# sub_module.net
KiCad netlist of a schematic drawn in EAGLE
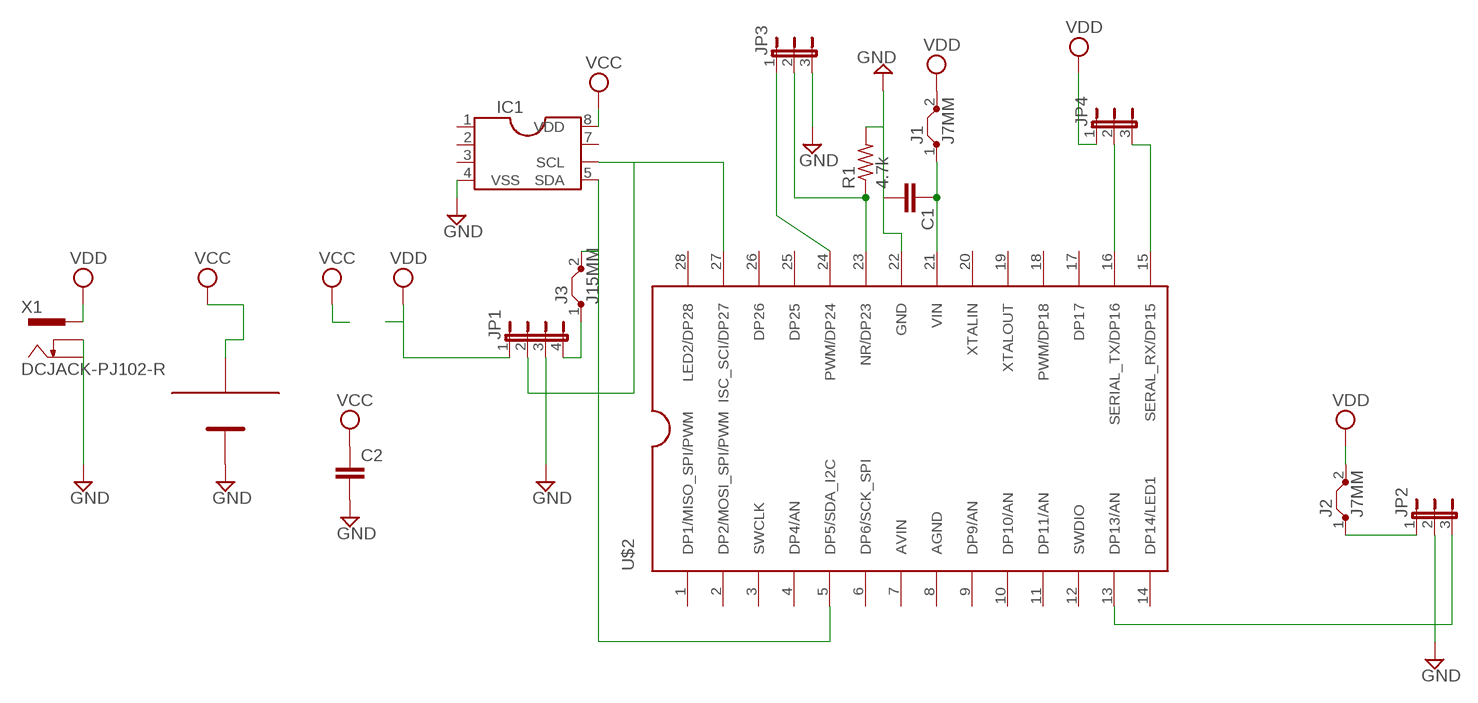
[diagram p0: schematic, sheet 1]

(export (version "E")
  (design (tool "Eeschema 10.0.6"))
  (components
    (comp (ref "C1")
      (value "C-EUC2012")
      (footprint "eagle-import:C2012")
      (libsource (lib "eagle-import") (part "C-EUC2012"))
    )
    (comp (ref "C2")
      (value "C-EUC2012")
      (footprint "eagle-import:C2012")
      (libsource (lib "eagle-import") (part "C-EUC2012"))
    )
    (comp (ref "IC1")
      (value "DIL8S")
      (footprint "eagle-import:SOCKET-08")
      (libsource (lib "eagle-import") (part "DIL8S"))
    )
    (comp (ref "J1")
      (value "J7MM")
      (footprint "eagle-import:07")
      (libsource (lib "eagle-import") (part "J7MM"))
    )
    (comp (ref "J2")
      (value "J7MM")
      (footprint "eagle-import:07")
      (libsource (lib "eagle-import") (part "J7MM"))
    )
    (comp (ref "J3")
      (value "J15MM")
      (footprint "eagle-import:15")
      (libsource (lib "eagle-import") (part "J15MM"))
    )
    (comp (ref "JP1")
      (value "JP4E")
      (footprint "eagle-import:JP4")
      (libsource (lib "eagle-import") (part "JP4E"))
    )
    (comp (ref "JP2")
      (value "JP2E")
      (footprint "eagle-import:JP2")
      (libsource (lib "eagle-import") (part "JP2E"))
    )
    (comp (ref "JP3")
      (value "JP2E")
      (footprint "eagle-import:JP2")
      (libsource (lib "eagle-import") (part "JP2E"))
    )
    (comp (ref "JP4")
      (value "JP2E")
      (footprint "eagle-import:JP2")
      (libsource (lib "eagle-import") (part "JP2E"))
    )
    (comp (ref "R1")
      (value "4.7k")
      (footprint "eagle-import:0207_2V")
      (libsource (lib "eagle-import") (part "R-US_0207/2V"))
    )
    (comp (ref "U$1")
      (value "CR2032-HOLDER2")
      (footprint "eagle-import:CR2032-HOLDER2")
      (libsource (lib "eagle-import") (part "CR2032-HOLDER2"))
    )
    (comp (ref "U$2")
      (value "LPC1114FDH28")
      (footprint "eagle-import:TSSOP28")
      (libsource (lib "eagle-import") (part "LPC1114FDH28"))
    )
    (comp (ref "X1")
      (value "DCJACK-PJ102-R")
      (footprint "eagle-import:PJ-102-R")
      (libsource (lib "eagle-import") (part "DCJACK-PJ102-R"))
    )
  )
  (nets
    (net (code "1") (name "/AGND") (class "Default")
      (node (ref "U$2") (pin "8") (pinfunction "AGND_8") (pintype "power_in"))
    )
    (net (code "2") (name "/AVIN") (class "Default")
      (node (ref "U$2") (pin "7") (pinfunction "AVIN_7") (pintype "power_in"))
    )
    (net (code "3") (name "GND") (class "Default")
      (node (ref "C1") (pin "2") (pinfunction "2_2") (pintype "passive"))
      (node (ref "C2") (pin "2") (pinfunction "2_2") (pintype "passive"))
      (node (ref "IC1") (pin "4") (pinfunction "VSS_4") (pintype "passive"))
      (node (ref "JP1") (pin "3") (pinfunction "3_3") (pintype "passive"))
      (node (ref "JP2") (pin "2") (pinfunction "2_2") (pintype "passive"))
      (node (ref "JP3") (pin "3") (pinfunction "3_3") (pintype "passive"))
      (node (ref "R1") (pin "2") (pinfunction "2_2") (pintype "passive"))
      (node (ref "U$1") (pin "GND") (pinfunction "GND_GND") (pintype "bidirectional"))
      (node (ref "U$2") (pin "22") (pinfunction "GND_22") (pintype "power_in"))
      (node (ref "X1") (pin "2") (pinfunction "2_2") (pintype "passive"))
      (node (ref "X1") (pin "3") (pinfunction "3_3") (pintype "passive"))
    )
    (net (code "4") (name "Net-(IC1-SCL)") (class "Default")
      (node (ref "IC1") (pin "6") (pinfunction "SCL_6") (pintype "passive"))
      (node (ref "JP1") (pin "2") (pinfunction "2_2") (pintype "passive"))
      (node (ref "U$2") (pin "27") (pinfunction "ISC_SCI/DP27_27") (pintype "bidirectional"))
    )
    (net (code "5") (name "Net-(IC1-SDA)") (class "Default")
      (node (ref "IC1") (pin "5") (pinfunction "SDA_5") (pintype "passive"))
      (node (ref "J3") (pin "2") (pinfunction "2_2") (pintype "passive"))
      (node (ref "U$2") (pin "5") (pinfunction "DP5/SDA_I2C_5") (pintype "bidirectional"))
    )
    (net (code "6") (name "Net-(J2-Pad1)") (class "Default")
      (node (ref "J2") (pin "1") (pinfunction "1_1") (pintype "passive"))
      (node (ref "JP2") (pin "1") (pinfunction "1_1") (pintype "passive"))
    )
    (net (code "7") (name "Net-(J3-Pad1)") (class "Default")
      (node (ref "J3") (pin "1") (pinfunction "1_1") (pintype "passive"))
      (node (ref "JP1") (pin "4") (pinfunction "4_4") (pintype "passive"))
    )
    (net (code "8") (name "Net-(U$2-DP13{slash}AN)") (class "Default")
      (node (ref "JP2") (pin "3") (pinfunction "3_3") (pintype "passive"))
      (node (ref "U$2") (pin "13") (pinfunction "DP13/AN_13") (pintype "bidirectional"))
    )
    (net (code "9") (name "Net-(U$2-NR{slash}DP23)") (class "Default")
      (node (ref "JP3") (pin "2") (pinfunction "2_2") (pintype "passive"))
      (node (ref "R1") (pin "1") (pinfunction "1_1") (pintype "passive"))
      (node (ref "U$2") (pin "23") (pinfunction "NR/DP23_23") (pintype "bidirectional"))
    )
    (net (code "10") (name "Net-(U$2-PWM{slash}DP24)") (class "Default")
      (node (ref "JP3") (pin "1") (pinfunction "1_1") (pintype "passive"))
      (node (ref "U$2") (pin "24") (pinfunction "PWM/DP24_24") (pintype "bidirectional"))
    )
    (net (code "11") (name "Net-(U$2-SERAL_RX{slash}DP15)") (class "Default")
      (node (ref "JP4") (pin "3") (pinfunction "3_3") (pintype "passive"))
      (node (ref "U$2") (pin "15") (pinfunction "SERAL_RX/DP15_15") (pintype "bidirectional"))
    )
    (net (code "12") (name "Net-(U$2-SERIAL_TX{slash}DP16)") (class "Default")
      (node (ref "JP4") (pin "2") (pinfunction "2_2") (pintype "passive"))
      (node (ref "U$2") (pin "16") (pinfunction "SERIAL_TX/DP16_16") (pintype "bidirectional"))
    )
    (net (code "13") (name "Net-(U$2-VIN)") (class "Default")
      (node (ref "C1") (pin "1") (pinfunction "1_1") (pintype "passive"))
      (node (ref "J1") (pin "1") (pinfunction "1_1") (pintype "passive"))
      (node (ref "U$2") (pin "21") (pinfunction "VIN_21") (pintype "power_in"))
    )
    (net (code "14") (name "VCC") (class "Default")
      (node (ref "C2") (pin "1") (pinfunction "1_1") (pintype "passive"))
      (node (ref "IC1") (pin "8") (pinfunction "VDD_8") (pintype "passive"))
      (node (ref "U$1") (pin "+3V") (pinfunction "+3V_+3V") (pintype "bidirectional"))
    )
    (net (code "15") (name "VDD") (class "Default")
      (node (ref "J1") (pin "2") (pinfunction "2_2") (pintype "passive"))
      (node (ref "J2") (pin "2") (pinfunction "2_2") (pintype "passive"))
      (node (ref "JP1") (pin "1") (pinfunction "1_1") (pintype "passive"))
      (node (ref "JP4") (pin "1") (pinfunction "1_1") (pintype "passive"))
      (node (ref "X1") (pin "1") (pinfunction "1_1") (pintype "passive"))
    )
    (net (code "16") (name "unconnected-(IC1-CLKOE-Pad1)") (class "Default")
      (node (ref "IC1") (pin "1") (pinfunction "CLKOE_1") (pintype "passive"))
    )
    (net (code "17") (name "unconnected-(IC1-CLKOUT-Pad2)") (class "Default")
      (node (ref "IC1") (pin "2") (pinfunction "CLKOUT_2") (pintype "passive"))
    )
    (net (code "18") (name "unconnected-(IC1-INT-Pad3)") (class "Default")
      (node (ref "IC1") (pin "3") (pinfunction "INT_3") (pintype "passive"))
    )
    (net (code "19") (name "unconnected-(IC1-V.C.-Pad7)") (class "Default")
      (node (ref "IC1") (pin "7") (pinfunction "V.C._7") (pintype "passive"))
    )
    (net (code "20") (name "unconnected-(U$2-DP1{slash}MISO_SPI{slash}PWM-Pad1)") (class "Default")
      (node (ref "U$2") (pin "1") (pinfunction "DP1/MISO_SPI/PWM_1") (pintype "bidirectional"))
    )
    (net (code "21") (name "unconnected-(U$2-DP2{slash}MOSI_SPI{slash}PWM-Pad2)") (class "Default")
      (node (ref "U$2") (pin "2") (pinfunction "DP2/MOSI_SPI/PWM_2") (pintype "bidirectional"))
    )
    (net (code "22") (name "unconnected-(U$2-DP4{slash}AN-Pad4)") (class "Default")
      (node (ref "U$2") (pin "4") (pinfunction "DP4/AN_4") (pintype "bidirectional"))
    )
    (net (code "23") (name "unconnected-(U$2-DP6{slash}SCK_SPI-Pad6)") (class "Default")
      (node (ref "U$2") (pin "6") (pinfunction "DP6/SCK_SPI_6") (pintype "bidirectional"))
    )
    (net (code "24") (name "unconnected-(U$2-DP9{slash}AN-Pad9)") (class "Default")
      (node (ref "U$2") (pin "9") (pinfunction "DP9/AN_9") (pintype "bidirectional"))
    )
    (net (code "25") (name "unconnected-(U$2-DP10{slash}AN-Pad10)") (class "Default")
      (node (ref "U$2") (pin "10") (pinfunction "DP10/AN_10") (pintype "bidirectional"))
    )
    (net (code "26") (name "unconnected-(U$2-DP11{slash}AN-Pad11)") (class "Default")
      (node (ref "U$2") (pin "11") (pinfunction "DP11/AN_11") (pintype "bidirectional"))
    )
    (net (code "27") (name "unconnected-(U$2-DP14{slash}LED1-Pad14)") (class "Default")
      (node (ref "U$2") (pin "14") (pinfunction "DP14/LED1_14") (pintype "bidirectional"))
    )
    (net (code "28") (name "unconnected-(U$2-DP17-Pad17)") (class "Default")
      (node (ref "U$2") (pin "17") (pinfunction "DP17_17") (pintype "bidirectional"))
    )
    (net (code "29") (name "unconnected-(U$2-DP25-Pad25)") (class "Default")
      (node (ref "U$2") (pin "25") (pinfunction "DP25_25") (pintype "bidirectional"))
    )
    (net (code "30") (name "unconnected-(U$2-DP26-Pad26)") (class "Default")
      (node (ref "U$2") (pin "26") (pinfunction "DP26_26") (pintype "bidirectional"))
    )
    (net (code "31") (name "unconnected-(U$2-LED2{slash}DP28-Pad28)") (class "Default")
      (node (ref "U$2") (pin "28") (pinfunction "LED2/DP28_28") (pintype "bidirectional"))
    )
    (net (code "32") (name "unconnected-(U$2-PWM{slash}DP18-Pad18)") (class "Default")
      (node (ref "U$2") (pin "18") (pinfunction "PWM/DP18_18") (pintype "bidirectional"))
    )
    (net (code "33") (name "unconnected-(U$2-SWCLK-Pad3)") (class "Default")
      (node (ref "U$2") (pin "3") (pinfunction "SWCLK_3") (pintype "bidirectional"))
    )
    (net (code "34") (name "unconnected-(U$2-SWDIO-Pad12)") (class "Default")
      (node (ref "U$2") (pin "12") (pinfunction "SWDIO_12") (pintype "bidirectional"))
    )
    (net (code "35") (name "unconnected-(U$2-XTALIN-Pad20)") (class "Default")
      (node (ref "U$2") (pin "20") (pinfunction "XTALIN_20") (pintype "input"))
    )
    (net (code "36") (name "unconnected-(U$2-XTALOUT-Pad19)") (class "Default")
      (node (ref "U$2") (pin "19") (pinfunction "XTALOUT_19") (pintype "output"))
    )
  )
)
